# Trigger.net
KiCad netlist of a schematic drawn in Altium Designer
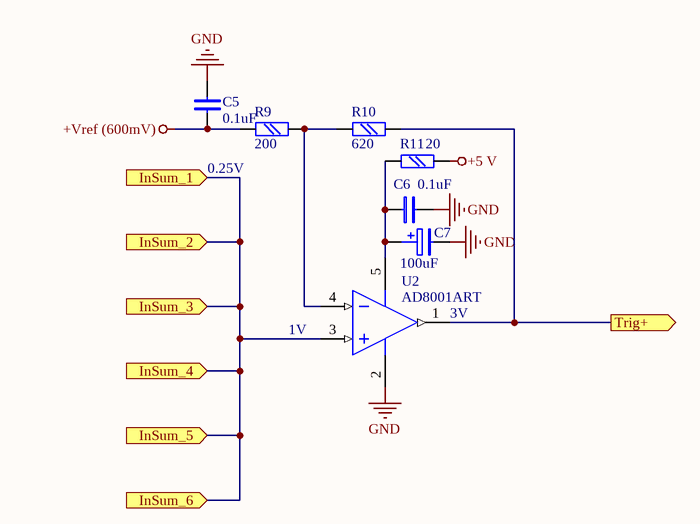
[diagram p0: Trigger.SchDoc]

(export (version "E")
  (design (tool "Eeschema 10.0.6"))
  (components
    (comp (ref "C5") (value "0.1uF") (footprint "chip0603") (libsource (lib "vDevice") (part "C")))
    (comp (ref "C6") (value "0.1uF") (footprint "chip0603") (libsource (lib "vDevice") (part "C")))
    (comp (ref "C7") (value "100uF") (footprint "CEL-SMD300") (libsource (lib "vDevice") (part "C POL")))
    (comp (ref "R9") (value "200") (footprint "chip0603") (libsource (lib "vDevice") (part "R")))
    (comp (ref "R10") (value "620") (footprint "chip0603") (libsource (lib "vDevice") (part "R")))
    (comp (ref "R11") (value "20") (footprint "chip0603") (libsource (lib "vDevice") (part "R")))
    (comp (ref "U2")
      (value "AD8001ART")
      (footprint "RT-5")
      (description "Low Cost, 300MHz Voltage Feedback Amplifier")
      (fields (field (name "PUBLISHER") "Altium Limited"))
      (libsource (lib "AD Operational Amplifier") (part "AD8055ART"))
    )
  )
  (nets
    (net (code "1") (name "+5 V") (class "Default")
      (node (ref "R11") (pin "1") (pinfunction "1_1") (pintype "passive"))
    )
    (net (code "2") (name "+Vref (600mV)") (class "Default")
      (node (ref "C5") (pin "2") (pinfunction "2_2") (pintype "passive"))
      (node (ref "R9") (pin "2") (pinfunction "2_2") (pintype "passive"))
    )
    (net (code "3") (name "/InSum_1") (class "Default")
      (node (ref "U2") (pin "3") (pinfunction "IN+_3") (pintype "input"))
    )
    (net (code "4") (name "/Trig+") (class "Default")
      (node (ref "R10") (pin "2") (pinfunction "2_2") (pintype "passive"))
      (node (ref "U2") (pin "1") (pinfunction "OUT_1") (pintype "output"))
    )
    (net (code "5") (name "GND") (class "Default")
      (node (ref "C5") (pin "1") (pinfunction "1_1") (pintype "passive"))
      (node (ref "C6") (pin "1") (pinfunction "1_1") (pintype "passive"))
      (node (ref "C7") (pin "-") (pinfunction "-_-") (pintype "passive"))
      (node (ref "U2") (pin "2") (pinfunction "V-_2") (pintype "power_in"))
    )
    (net (code "6") (name "Net-(U2-IN-)") (class "Default")
      (node (ref "R10") (pin "1") (pinfunction "1_1") (pintype "passive"))
      (node (ref "R9") (pin "1") (pinfunction "1_1") (pintype "passive"))
      (node (ref "U2") (pin "4") (pinfunction "IN-_4") (pintype "input"))
    )
    (net (code "7") (name "Net-(U2-V+)") (class "Default")
      (node (ref "C6") (pin "2") (pinfunction "2_2") (pintype "passive"))
      (node (ref "C7") (pin "+") (pinfunction "+_+") (pintype "passive"))
      (node (ref "R11") (pin "2") (pinfunction "2_2") (pintype "passive"))
      (node (ref "U2") (pin "5") (pinfunction "V+_5") (pintype "power_in"))
    )
  )
)
